# CAN_Hub_1.net
KiCad netlist of a schematic drawn in Altium Designer
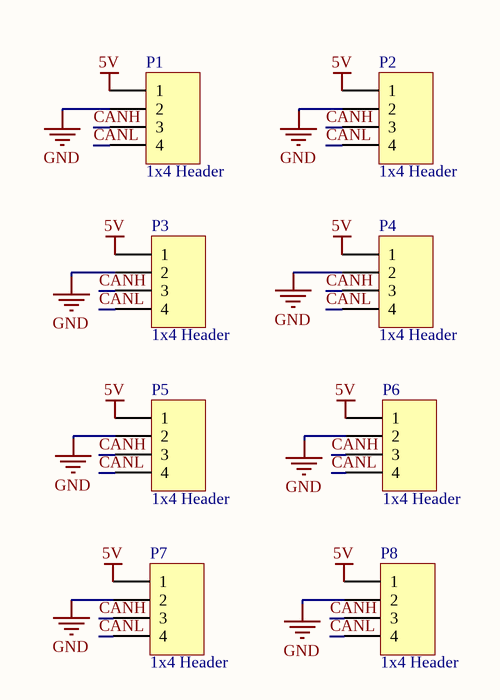
[diagram p0: CAN Hub 1.SchDoc]

(export (version "E")
  (design (tool "Eeschema 10.0.6"))
  (components
    (comp (ref "P1")
      (value "1x4 Header")
      (footprint "HDR1X4")
      (description "1x4 Pin Header")
      (libsource (lib "GeneralConnectors") (part "1x4 Header"))
    )
    (comp (ref "P2")
      (value "1x4 Header")
      (footprint "HDR1X4")
      (description "1x4 Pin Header")
      (libsource (lib "GeneralConnectors") (part "1x4 Header"))
    )
    (comp (ref "P3")
      (value "1x4 Header")
      (footprint "HDR1X4")
      (description "1x4 Pin Header")
      (libsource (lib "GeneralConnectors") (part "1x4 Header"))
    )
    (comp (ref "P4")
      (value "1x4 Header")
      (footprint "HDR1X4")
      (description "1x4 Pin Header")
      (libsource (lib "GeneralConnectors") (part "1x4 Header"))
    )
    (comp (ref "P5")
      (value "1x4 Header")
      (footprint "HDR1X4")
      (description "1x4 Pin Header")
      (libsource (lib "GeneralConnectors") (part "1x4 Header"))
    )
    (comp (ref "P6")
      (value "1x4 Header")
      (footprint "HDR1X4")
      (description "1x4 Pin Header")
      (libsource (lib "GeneralConnectors") (part "1x4 Header"))
    )
    (comp (ref "P7")
      (value "1x4 Header")
      (footprint "HDR1X4")
      (description "1x4 Pin Header")
      (libsource (lib "GeneralConnectors") (part "1x4 Header"))
    )
    (comp (ref "P8")
      (value "1x4 Header")
      (footprint "HDR1X4")
      (description "1x4 Pin Header")
      (libsource (lib "GeneralConnectors") (part "1x4 Header"))
    )
  )
  (nets
    (net (code "1") (name "/CANH") (class "Default")
      (node (ref "P1") (pin "3") (pinfunction "3_3") (pintype "passive"))
      (node (ref "P2") (pin "3") (pinfunction "3_3") (pintype "passive"))
      (node (ref "P3") (pin "3") (pinfunction "3_3") (pintype "passive"))
      (node (ref "P4") (pin "3") (pinfunction "3_3") (pintype "passive"))
      (node (ref "P5") (pin "3") (pinfunction "3_3") (pintype "passive"))
      (node (ref "P6") (pin "3") (pinfunction "3_3") (pintype "passive"))
      (node (ref "P7") (pin "3") (pinfunction "3_3") (pintype "passive"))
      (node (ref "P8") (pin "3") (pinfunction "3_3") (pintype "passive"))
    )
    (net (code "2") (name "/CANL") (class "Default")
      (node (ref "P1") (pin "4") (pinfunction "4_4") (pintype "passive"))
      (node (ref "P2") (pin "4") (pinfunction "4_4") (pintype "passive"))
      (node (ref "P3") (pin "4") (pinfunction "4_4") (pintype "passive"))
      (node (ref "P4") (pin "4") (pinfunction "4_4") (pintype "passive"))
      (node (ref "P5") (pin "4") (pinfunction "4_4") (pintype "passive"))
      (node (ref "P6") (pin "4") (pinfunction "4_4") (pintype "passive"))
      (node (ref "P7") (pin "4") (pinfunction "4_4") (pintype "passive"))
      (node (ref "P8") (pin "4") (pinfunction "4_4") (pintype "passive"))
    )
    (net (code "3") (name "5V") (class "Default")
      (node (ref "P1") (pin "1") (pinfunction "1_1") (pintype "passive"))
      (node (ref "P2") (pin "1") (pinfunction "1_1") (pintype "passive"))
      (node (ref "P3") (pin "1") (pinfunction "1_1") (pintype "passive"))
      (node (ref "P4") (pin "1") (pinfunction "1_1") (pintype "passive"))
      (node (ref "P5") (pin "1") (pinfunction "1_1") (pintype "passive"))
      (node (ref "P6") (pin "1") (pinfunction "1_1") (pintype "passive"))
      (node (ref "P7") (pin "1") (pinfunction "1_1") (pintype "passive"))
      (node (ref "P8") (pin "1") (pinfunction "1_1") (pintype "passive"))
    )
    (net (code "4") (name "GND") (class "Default")
      (node (ref "P1") (pin "2") (pinfunction "2_2") (pintype "passive"))
      (node (ref "P2") (pin "2") (pinfunction "2_2") (pintype "passive"))
      (node (ref "P3") (pin "2") (pinfunction "2_2") (pintype "passive"))
      (node (ref "P4") (pin "2") (pinfunction "2_2") (pintype "passive"))
      (node (ref "P5") (pin "2") (pinfunction "2_2") (pintype "passive"))
      (node (ref "P6") (pin "2") (pinfunction "2_2") (pintype "passive"))
      (node (ref "P7") (pin "2") (pinfunction "2_2") (pintype "passive"))
      (node (ref "P8") (pin "2") (pinfunction "2_2") (pintype "passive"))
    )
  )
)
